# 2_SIM.net
KiCad netlist of a schematic drawn in Altium Designer
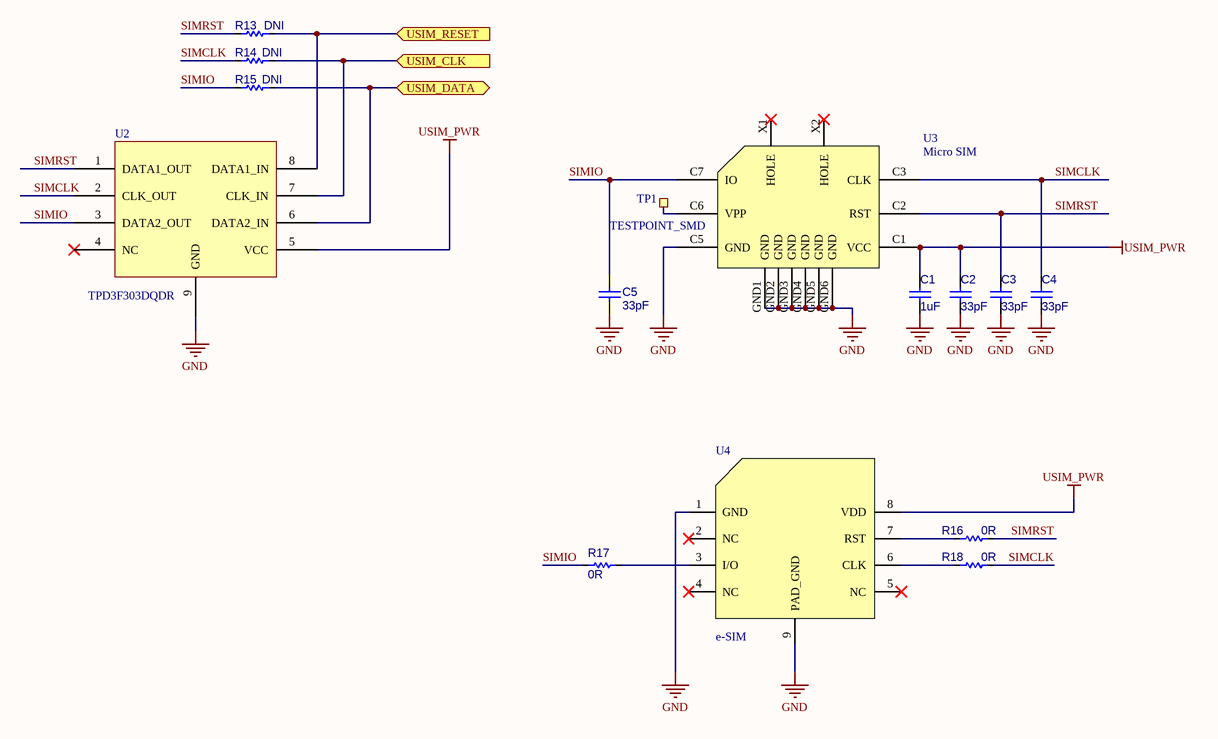
[diagram p0: 2.SIM.SchDoc]

(export (version "E")
  (design (tool "Eeschema 10.0.6"))
  (components
    (comp (ref "C1")
      (value "1uF")
      (footprint "CAP-0402")
      (description "Ceramic CAP 0402(1005)")
      (libsource (lib "Scott_lib") (part "CAP-0402"))
    )
    (comp (ref "C2")
      (value "33pF")
      (footprint "CAP-0402")
      (description "Ceramic CAP 0402(1005)")
      (libsource (lib "Scott_lib") (part "CAP-0402"))
    )
    (comp (ref "C3")
      (value "33pF")
      (footprint "CAP-0402")
      (description "Ceramic CAP 0402(1005)")
      (libsource (lib "Scott_lib") (part "CAP-0402"))
    )
    (comp (ref "C4")
      (value "33pF")
      (footprint "CAP-0402")
      (description "Ceramic CAP 0402(1005)")
      (libsource (lib "Scott_lib") (part "CAP-0402"))
    )
    (comp (ref "C5")
      (value "33pF")
      (footprint "CAP-0402")
      (description "Ceramic CAP 0402(1005)")
      (libsource (lib "Scott_lib") (part "CAP-0402"))
    )
    (comp (ref "R13")
      (value "DNI")
      (footprint "RES-0402")
      (description "RES-0402")
      (libsource (lib "Scott_lib") (part "RES-0402"))
    )
    (comp (ref "R14")
      (value "DNI")
      (footprint "RES-0402")
      (description "RES-0402")
      (libsource (lib "Scott_lib") (part "RES-0402"))
    )
    (comp (ref "R15")
      (value "DNI")
      (footprint "RES-0402")
      (description "RES-0402")
      (libsource (lib "Scott_lib") (part "RES-0402"))
    )
    (comp (ref "R16")
      (value "0R")
      (footprint "RES-0402")
      (description "RES-0402")
      (libsource (lib "Scott_lib") (part "RES-0402"))
    )
    (comp (ref "R17")
      (value "0R")
      (footprint "RES-0402")
      (description "RES-0402")
      (libsource (lib "Scott_lib") (part "RES-0402"))
    )
    (comp (ref "R18")
      (value "0R")
      (footprint "RES-0402")
      (description "RES-0402")
      (libsource (lib "Scott_lib") (part "RES-0402"))
    )
    (comp (ref "TP1")
      (value "TESTPOINT_SMD")
      (footprint "TP(SMD)-1PI")
      (description "TEST POINT")
      (libsource (lib "Scott_lib") (part "TESTPOINT_SMD"))
    )
    (comp (ref "U2")
      (value "TPD3F303DQDR")
      (footprint "PWSON08(0.4/1.45X1.8)")
      (description "ESD Protection SIM")
      (libsource (lib "Isaac_library") (part "TPD3F303DQDR"))
    )
    (comp (ref "U3")
      (value "Micro SIM")
      (footprint "0786463001")
      (description "Micro SIM SMT 1.45mm Push/Pull")
      (libsource (lib "AM_Starter_kit") (part "Micro SIM"))
    )
    (comp (ref "U4")
      (value "e-SIM")
      (footprint "SON08(1.27/6X5)")
      (libsource (lib "WM-N400MSE_Starter_kit") (part "e-SIM"))
    )
  )
  (nets
    (net (code "1") (name "/SIMCLK") (class "Default")
      (node (ref "C4") (pin "2") (pinfunction "2_2") (pintype "passive"))
      (node (ref "R14") (pin "2") (pinfunction "2_2") (pintype "passive"))
      (node (ref "R18") (pin "2") (pinfunction "2_2") (pintype "passive"))
      (node (ref "U2") (pin "2") (pinfunction "CLK_OUT_2") (pintype "passive"))
      (node (ref "U3") (pin "C3") (pinfunction "CLK_C3") (pintype "passive"))
    )
    (net (code "2") (name "/SIMIO") (class "Default")
      (node (ref "C5") (pin "2") (pinfunction "2_2") (pintype "passive"))
      (node (ref "R15") (pin "2") (pinfunction "2_2") (pintype "passive"))
      (node (ref "R17") (pin "1") (pinfunction "1_1") (pintype "passive"))
      (node (ref "U2") (pin "3") (pinfunction "DATA2_OUT_3") (pintype "passive"))
      (node (ref "U3") (pin "C7") (pinfunction "IO_C7") (pintype "passive"))
    )
    (net (code "3") (name "/SIMRST") (class "Default")
      (node (ref "C3") (pin "2") (pinfunction "2_2") (pintype "passive"))
      (node (ref "R13") (pin "2") (pinfunction "2_2") (pintype "passive"))
      (node (ref "R16") (pin "2") (pinfunction "2_2") (pintype "passive"))
      (node (ref "U2") (pin "1") (pinfunction "DATA1_OUT_1") (pintype "passive"))
      (node (ref "U3") (pin "C2") (pinfunction "RST_C2") (pintype "passive"))
    )
    (net (code "4") (name "/USIM_CLK") (class "Default")
      (node (ref "R14") (pin "1") (pinfunction "1_1") (pintype "passive"))
      (node (ref "U2") (pin "7") (pinfunction "CLK_IN_7") (pintype "passive"))
    )
    (net (code "5") (name "/USIM_DATA") (class "Default")
      (node (ref "R15") (pin "1") (pinfunction "1_1") (pintype "passive"))
      (node (ref "U2") (pin "6") (pinfunction "DATA2_IN_6") (pintype "passive"))
    )
    (net (code "6") (name "/USIM_RESET") (class "Default")
      (node (ref "R13") (pin "1") (pinfunction "1_1") (pintype "passive"))
      (node (ref "U2") (pin "8") (pinfunction "DATA1_IN_8") (pintype "passive"))
    )
    (net (code "7") (name "GND") (class "Default")
      (node (ref "C1") (pin "1") (pinfunction "1_1") (pintype "passive"))
      (node (ref "C2") (pin "1") (pinfunction "1_1") (pintype "passive"))
      (node (ref "C3") (pin "1") (pinfunction "1_1") (pintype "passive"))
      (node (ref "C4") (pin "1") (pinfunction "1_1") (pintype "passive"))
      (node (ref "C5") (pin "1") (pinfunction "1_1") (pintype "passive"))
      (node (ref "U2") (pin "9") (pinfunction "GND_9") (pintype "passive"))
      (node (ref "U3") (pin "C5") (pinfunction "GND_C5") (pintype "passive"))
      (node (ref "U3") (pin "GND1") (pinfunction "GND_GND1") (pintype "passive"))
      (node (ref "U3") (pin "GND2") (pinfunction "GND_GND2") (pintype "passive"))
      (node (ref "U3") (pin "GND3") (pinfunction "GND_GND3") (pintype "passive"))
      (node (ref "U3") (pin "GND4") (pinfunction "GND_GND4") (pintype "passive"))
      (node (ref "U3") (pin "GND5") (pinfunction "GND_GND5") (pintype "passive"))
      (node (ref "U3") (pin "GND6") (pinfunction "GND_GND6") (pintype "passive"))
      (node (ref "U4") (pin "1") (pinfunction "GND_1") (pintype "passive"))
      (node (ref "U4") (pin "9") (pinfunction "PAD_GND_9") (pintype "passive"))
    )
    (net (code "8") (name "Net-(TP1-TETSPOINT)") (class "Default")
      (node (ref "TP1") (pin "1") (pinfunction "TETSPOINT_1") (pintype "passive"))
      (node (ref "U3") (pin "C6") (pinfunction "VPP_C6") (pintype "passive"))
    )
    (net (code "9") (name "Net-(U4-CLK)") (class "Default")
      (node (ref "R18") (pin "1") (pinfunction "1_1") (pintype "passive"))
      (node (ref "U4") (pin "6") (pinfunction "CLK_6") (pintype "passive"))
    )
    (net (code "10") (name "Net-(U4-I{slash}O)") (class "Default")
      (node (ref "R17") (pin "2") (pinfunction "2_2") (pintype "passive"))
      (node (ref "U4") (pin "3") (pinfunction "I/O_3") (pintype "passive"))
    )
    (net (code "11") (name "Net-(U4-RST)") (class "Default")
      (node (ref "R16") (pin "1") (pinfunction "1_1") (pintype "passive"))
      (node (ref "U4") (pin "7") (pinfunction "RST_7") (pintype "passive"))
    )
    (net (code "12") (name "USIM_PWR") (class "Default")
      (node (ref "C1") (pin "2") (pinfunction "2_2") (pintype "passive"))
      (node (ref "C2") (pin "2") (pinfunction "2_2") (pintype "passive"))
      (node (ref "U2") (pin "5") (pinfunction "VCC_5") (pintype "passive"))
      (node (ref "U3") (pin "C1") (pinfunction "VCC_C1") (pintype "passive"))
      (node (ref "U4") (pin "8") (pinfunction "VDD_8") (pintype "passive"))
    )
    (net (code "13") (name "unconnected-(U2-NC-Pad4)") (class "Default")
      (node (ref "U2") (pin "4") (pinfunction "NC_4") (pintype "passive+no_connect"))
    )
    (net (code "14") (name "unconnected-(U3-HOLE-PadX1)") (class "Default")
      (node (ref "U3") (pin "X1") (pinfunction "HOLE_X1") (pintype "passive+no_connect"))
    )
    (net (code "15") (name "unconnected-(U3-HOLE-PadX2)") (class "Default")
      (node (ref "U3") (pin "X2") (pinfunction "HOLE_X2") (pintype "passive+no_connect"))
    )
    (net (code "16") (name "unconnected-(U4-NC-Pad2)") (class "Default")
      (node (ref "U4") (pin "2") (pinfunction "NC_2") (pintype "passive+no_connect"))
    )
    (net (code "17") (name "unconnected-(U4-NC-Pad4)") (class "Default")
      (node (ref "U4") (pin "4") (pinfunction "NC_4") (pintype "passive+no_connect"))
    )
    (net (code "18") (name "unconnected-(U4-NC-Pad5)") (class "Default")
      (node (ref "U4") (pin "5") (pinfunction "NC_5") (pintype "passive+no_connect"))
    )
  )
)
